# CanSat1_Sch.net
KiCad netlist of a schematic drawn in Altium Designer
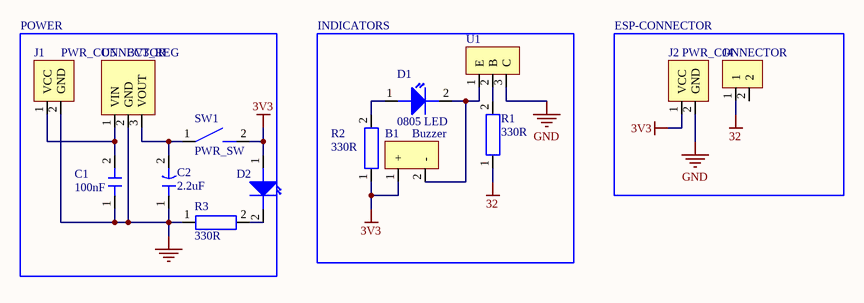
[diagram p0: CanSat1_Sch.SchDoc]

(export (version "E")
  (design (tool "Eeschema 10.0.6"))
  (components
    (comp (ref "B1")
      (value "Buzzer")
      (footprint "BUZZER")
      (description "Active buzzer")
      (libsource (lib "CanSat1_SchLib") (part "BUZZER"))
    )
    (comp (ref "C1")
      (value "100nF")
      (footprint "CERAMIC CAP")
      (description "Ceramic through-hole capacitor")
      (libsource (lib "CanSat1_SchLib") (part "CAP"))
    )
    (comp (ref "C2")
      (value "2.2uF")
      (footprint "Electrolytic capacitor 2mm")
      (description "Throug-hole 2.2uF")
      (libsource (lib "CanSat1_SchLib") (part "E_CAP_2.2uF"))
    )
    (comp (ref "D1")
      (value "0805 LED")
      (footprint "3mm_LED")
      (description "Through-hole LED")
      (libsource (lib "CanSat1_SchLib") (part "LED"))
    )
    (comp (ref "D2")
      (value "0805 LED")
      (footprint "3mm_LED")
      (description "Through-hole LED")
      (libsource (lib "CanSat1_SchLib") (part "LED"))
    )
    (comp (ref "J1")
      (value "PWR_CONNECTOR")
      (footprint "BATT")
      (description "THT Connector")
      (libsource (lib "CanSat1_SchLib") (part "PWR-CONN"))
    )
    (comp (ref "J2")
      (value "PWR_CONNECTOR")
      (footprint "BATT")
      (description "THT Connector")
      (libsource (lib "CanSat1_SchLib") (part "PWR-CONN"))
    )
    (comp (ref "J4")
      (value "2x1_CONN")
      (footprint "CONN2x1_2.54mm")
      (description "THT 2x1 2.54mm CONN")
      (libsource (lib "CanSat1_SchLib") (part "CONN 2x1"))
    )
    (comp (ref "R1")
      (value "330R")
      (footprint "THT RESISTOR")
      (description "Through-hole resistor")
      (libsource (lib "CanSat1_SchLib") (part "Resistor"))
    )
    (comp (ref "R2")
      (value "330R")
      (footprint "THT RESISTOR")
      (description "Through-hole resistor")
      (libsource (lib "CanSat1_SchLib") (part "Resistor"))
    )
    (comp (ref "R3")
      (value "330R")
      (footprint "THT RESISTOR")
      (description "Through-hole resistor")
      (libsource (lib "CanSat1_SchLib") (part "Resistor"))
    )
    (comp (ref "SW1")
      (value "PWR_SW")
      (footprint "PWR-SW")
      (description "Mechanical through-hole switch")
      (libsource (lib "CanSat1_SchLib") (part "SWITCH"))
    )
    (comp (ref "U1")
      (value "NPN Transistor")
      (footprint "CanSat1PcbLib:2N2222A")
      (description "Through-hole NPN Transistor")
      (libsource (lib "CanSat1_SchLib") (part "2N2222"))
    )
    (comp (ref "U5")
      (value "3V3_REG")
      (footprint "LF33CV")
      (description "Through-hole 3.3V regulator")
      (libsource (lib "CanSat1_SchLib") (part "LF33CV"))
    )
  )
  (nets
    (net (code "1") (name "3V3") (class "Default")
      (node (ref "B1") (pin "1") (pinfunction "+_1") (pintype "passive"))
      (node (ref "D2") (pin "1") (pinfunction "A_1") (pintype "passive"))
      (node (ref "J2") (pin "1") (pinfunction "VCC_1") (pintype "passive"))
      (node (ref "R2") (pin "1") (pinfunction "1_1") (pintype "passive"))
      (node (ref "SW1") (pin "2") (pinfunction "+_2") (pintype "passive"))
    )
    (net (code "2") (name "32") (class "Default")
      (node (ref "J4") (pin "1") (pinfunction "1_1") (pintype "passive"))
      (node (ref "R1") (pin "1") (pinfunction "1_1") (pintype "passive"))
    )
    (net (code "3") (name "GND") (class "Default")
      (node (ref "C1") (pin "1") (pinfunction "+_1") (pintype "passive"))
      (node (ref "C2") (pin "1") (pinfunction "+_1") (pintype "passive"))
      (node (ref "J1") (pin "2") (pinfunction "GND_2") (pintype "passive"))
      (node (ref "J2") (pin "2") (pinfunction "GND_2") (pintype "passive"))
      (node (ref "R3") (pin "1") (pinfunction "1_1") (pintype "passive"))
      (node (ref "U1") (pin "3") (pinfunction "C_3") (pintype "passive"))
      (node (ref "U5") (pin "2") (pinfunction "GND_2") (pintype "passive"))
    )
    (net (code "4") (name "Net-(B1--)") (class "Default")
      (node (ref "B1") (pin "2") (pinfunction "-_2") (pintype "passive"))
      (node (ref "D1") (pin "2") (pinfunction "K_2") (pintype "passive"))
      (node (ref "U1") (pin "1") (pinfunction "E_1") (pintype "passive"))
    )
    (net (code "5") (name "Net-(C1--)") (class "Default")
      (node (ref "C1") (pin "2") (pinfunction "-_2") (pintype "passive"))
      (node (ref "J1") (pin "1") (pinfunction "VCC_1") (pintype "passive"))
      (node (ref "U5") (pin "1") (pinfunction "VIN_1") (pintype "passive"))
    )
    (net (code "6") (name "Net-(C2--)") (class "Default")
      (node (ref "C2") (pin "2") (pinfunction "-_2") (pintype "passive"))
      (node (ref "SW1") (pin "1") (pinfunction "+_1") (pintype "passive"))
      (node (ref "U5") (pin "3") (pinfunction "VOUT_3") (pintype "passive"))
    )
    (net (code "7") (name "Net-(D1-A)") (class "Default")
      (node (ref "D1") (pin "1") (pinfunction "A_1") (pintype "passive"))
      (node (ref "R2") (pin "2") (pinfunction "2_2") (pintype "passive"))
    )
    (net (code "8") (name "Net-(D2-K)") (class "Default")
      (node (ref "D2") (pin "2") (pinfunction "K_2") (pintype "passive"))
      (node (ref "R3") (pin "2") (pinfunction "2_2") (pintype "passive"))
    )
    (net (code "9") (name "Net-(U1-B)") (class "Default")
      (node (ref "R1") (pin "2") (pinfunction "2_2") (pintype "passive"))
      (node (ref "U1") (pin "2") (pinfunction "B_2") (pintype "passive"))
    )
    (net (code "10") (name "unconnected-(J4-Pad2)") (class "Default")
      (node (ref "J4") (pin "2") (pinfunction "2_2") (pintype "passive"))
    )
  )
)
